# rlabTT.net
KiCad netlist of a schematic drawn in EAGLE
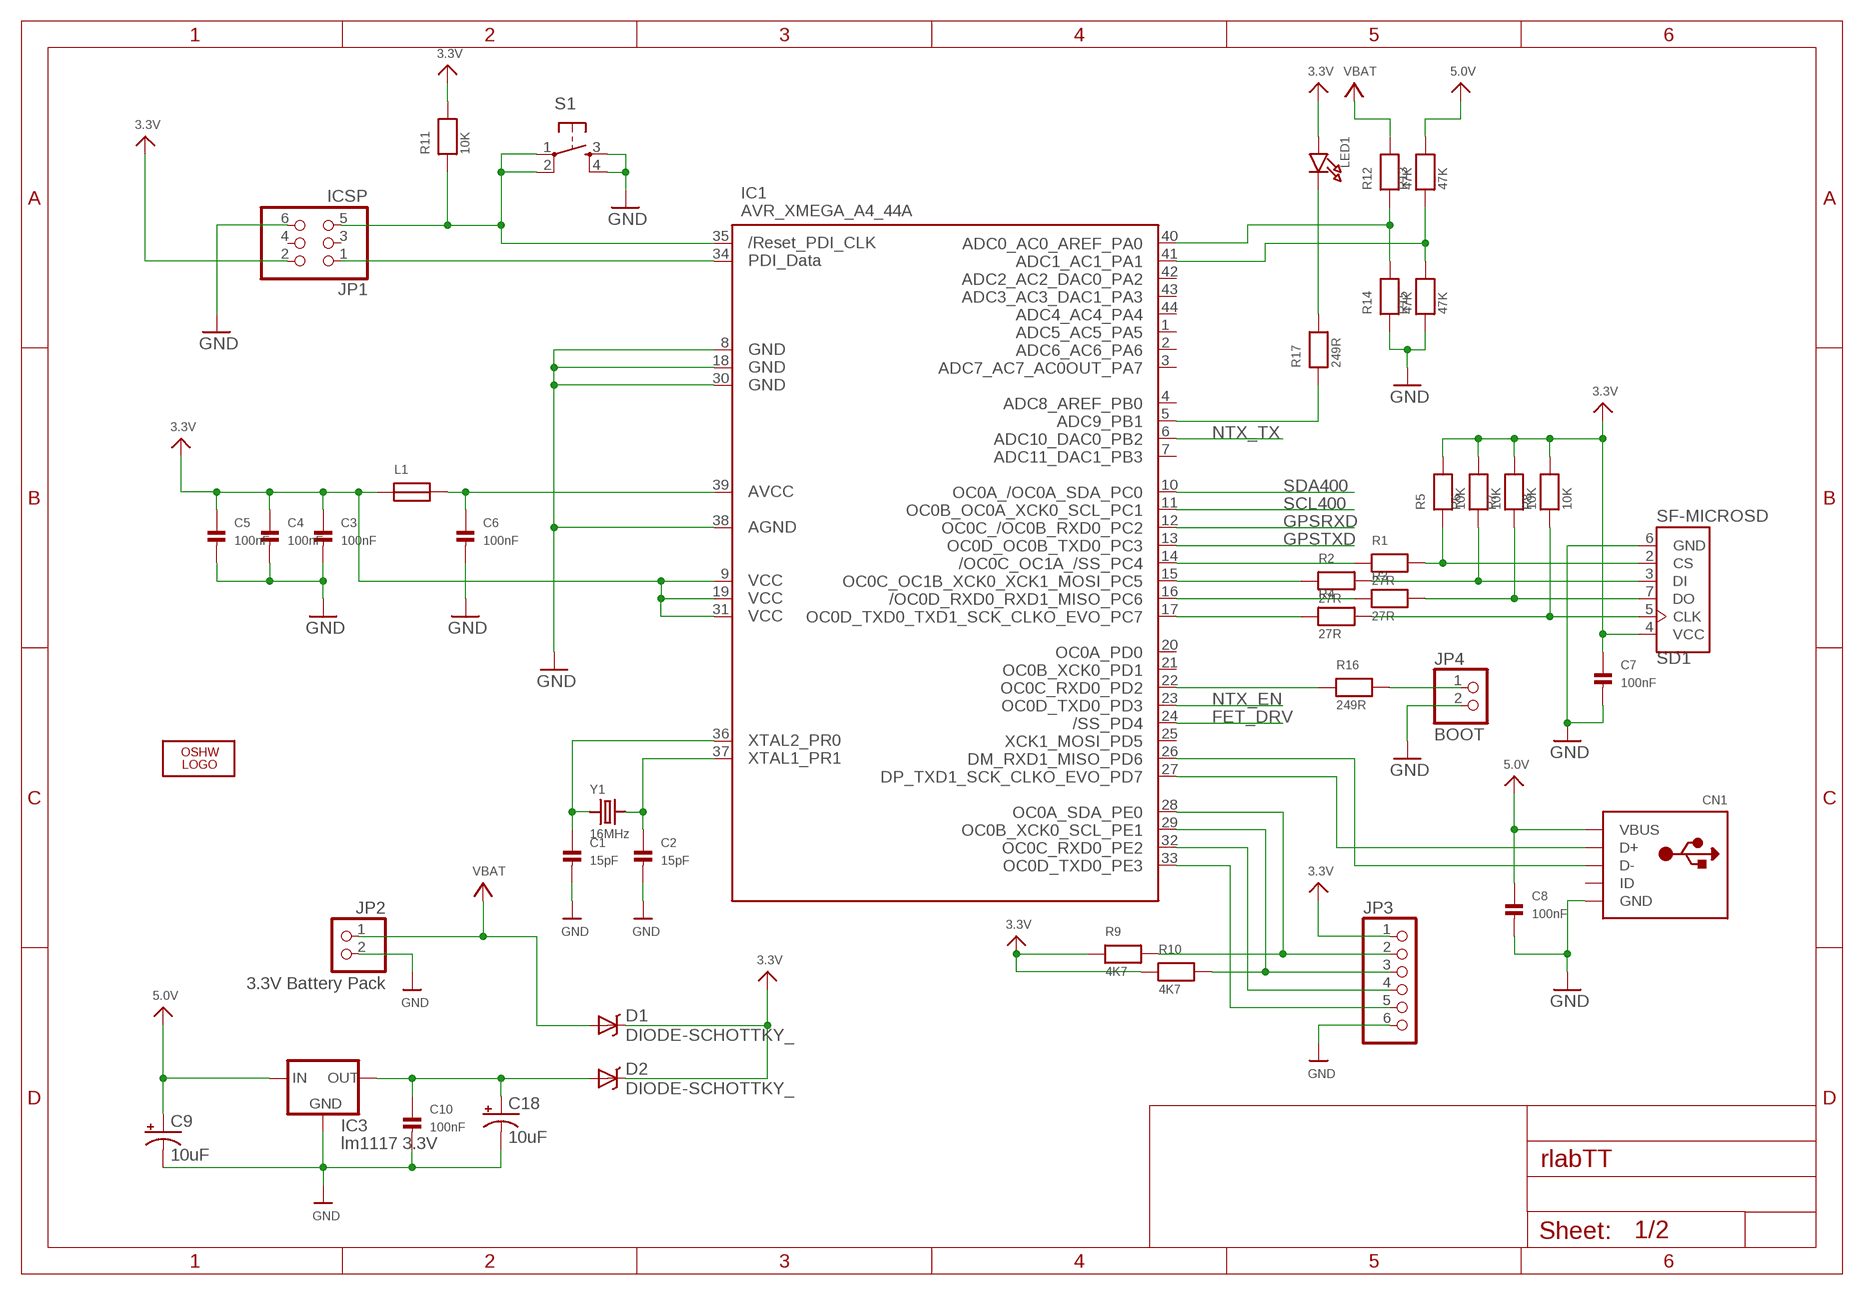
[diagram p0: schematic, sheet 1]
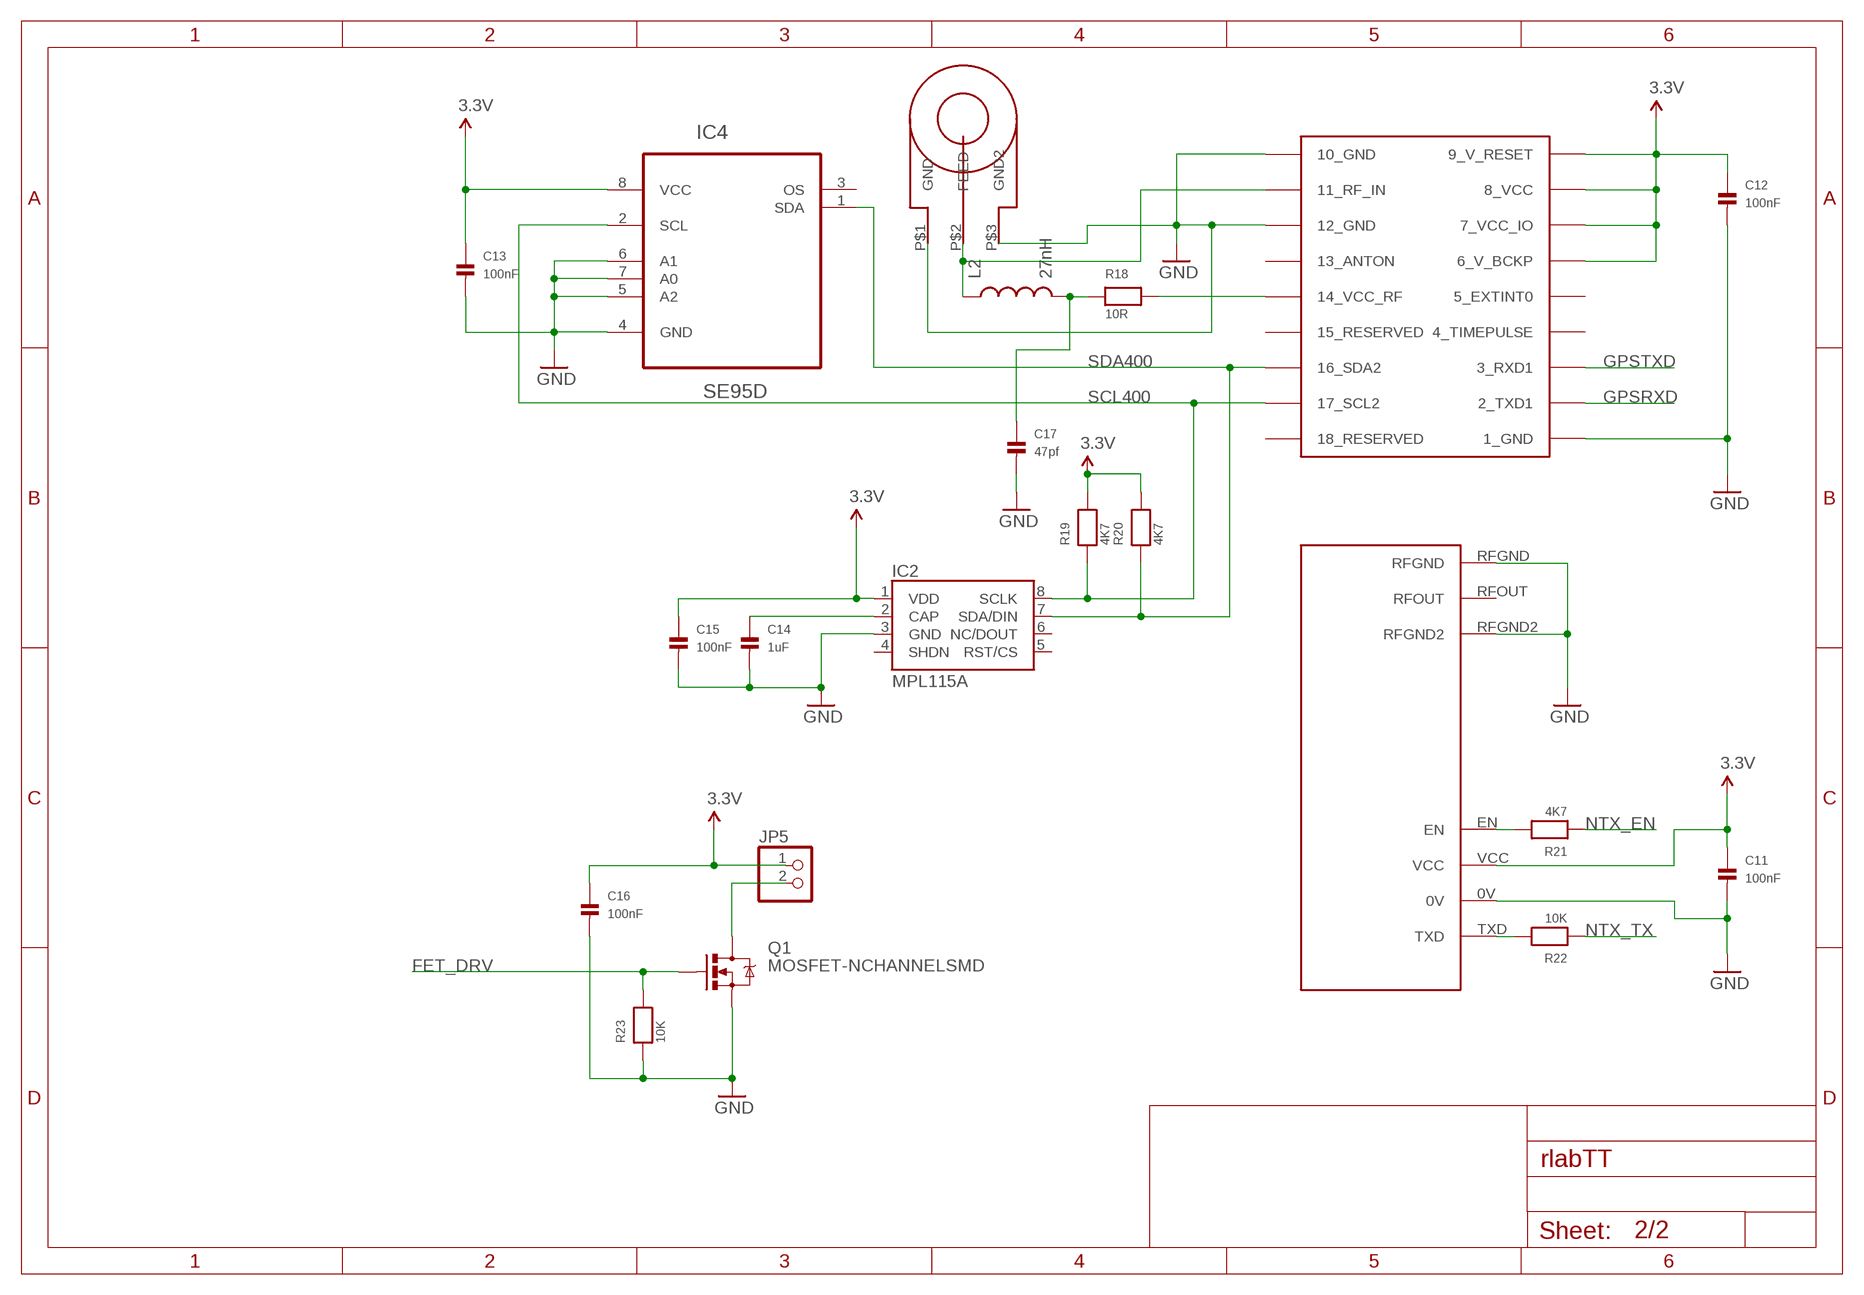
[diagram p1: schematic, sheet 2]

(export (version "E")
  (design (tool "Eeschema 10.0.6"))
  (components
    (comp (ref "C1")
      (value "15pF")
      (footprint "eagle-import:0603")
      (libsource (lib "eagle-import") (part "CAP_CERAMIC0603"))
    )
    (comp (ref "C2")
      (value "15pF")
      (footprint "eagle-import:0603")
      (libsource (lib "eagle-import") (part "CAP_CERAMIC0603"))
    )
    (comp (ref "C3")
      (value "100nF")
      (footprint "eagle-import:0603")
      (libsource (lib "eagle-import") (part "CAP_CERAMIC0603"))
    )
    (comp (ref "C4")
      (value "100nF")
      (footprint "eagle-import:0603")
      (libsource (lib "eagle-import") (part "CAP_CERAMIC0603"))
    )
    (comp (ref "C5")
      (value "100nF")
      (footprint "eagle-import:0603")
      (libsource (lib "eagle-import") (part "CAP_CERAMIC0603"))
    )
    (comp (ref "C6")
      (value "100nF")
      (footprint "eagle-import:0603")
      (libsource (lib "eagle-import") (part "CAP_CERAMIC0603"))
    )
    (comp (ref "C7")
      (value "100nF")
      (footprint "eagle-import:0603")
      (libsource (lib "eagle-import") (part "CAP_CERAMIC0603"))
    )
    (comp (ref "C8")
      (value "100nF")
      (footprint "eagle-import:0603")
      (libsource (lib "eagle-import") (part "CAP_CERAMIC0603"))
    )
    (comp (ref "C9")
      (value "10uF")
      (footprint "eagle-import:EIA3528")
      (libsource (lib "eagle-import") (part "CAP_POL3528"))
    )
    (comp (ref "C10")
      (value "100nF")
      (footprint "eagle-import:0603")
      (libsource (lib "eagle-import") (part "CAP_CERAMIC0603"))
    )
    (comp (ref "C18")
      (value "10uF")
      (footprint "eagle-import:EIA3528")
      (libsource (lib "eagle-import") (part "CAP_POL3528"))
    )
    (comp (ref "CN1")
      (value "USBMINIB")
      (footprint "eagle-import:USB-MINIB")
      (libsource (lib "eagle-import") (part "USBMINIB"))
    )
    (comp (ref "D1")
      (value "DIODE-SCHOTTKY_")
      (footprint "eagle-import:SMA-DIODE")
      (libsource (lib "eagle-import") (part "DIODE-SCHOTTKY_"))
    )
    (comp (ref "D2")
      (value "DIODE-SCHOTTKY_")
      (footprint "eagle-import:SMA-DIODE")
      (libsource (lib "eagle-import") (part "DIODE-SCHOTTKY_"))
    )
    (comp (ref "IC1")
      (value "AVR_XMEGA_A4_44A")
      (footprint "eagle-import:TQFP44")
      (libsource (lib "eagle-import") (part "AVR_XMEGA_A4_44A"))
    )
    (comp (ref "IC3")
      (value "lm1117 3.3V")
      (footprint "eagle-import:SOT223")
      (libsource (lib "eagle-import") (part "LM1117"))
    )
    (comp (ref "JP1")
      (value "ICSP")
      (footprint "eagle-import:2X03_90")
      (libsource (lib "eagle-import") (part "PINHD-2X3/90"))
    )
    (comp (ref "JP2")
      (value "3.3V Battery Pack")
      (footprint "eagle-import:1X02_90")
      (libsource (lib "eagle-import") (part "PINHD-1X2/90"))
    )
    (comp (ref "JP3")
      (value "PINHD-1X6/90")
      (footprint "eagle-import:1X06_90")
      (libsource (lib "eagle-import") (part "PINHD-1X6/90"))
    )
    (comp (ref "JP4")
      (value "BOOT")
      (footprint "eagle-import:1X02_90")
      (libsource (lib "eagle-import") (part "PINHD-1X2/90"))
    )
    (comp (ref "L1")
      (value "FERRITE")
      (footprint "eagle-import:0603")
      (libsource (lib "eagle-import") (part "FERRITE"))
    )
    (comp (ref "LED1")
      (value "LED0603")
      (footprint "eagle-import:CHIPLED_0603")
      (libsource (lib "eagle-import") (part "LED0603"))
    )
    (comp (ref "LOGO1")
      (value "OSHW_LOGO_8MILX0150-NT")
      (footprint "eagle-import:OSHW_8X150_NOTEXT")
      (libsource (lib "eagle-import") (part "OSHW_LOGO_8MILX0150-NT"))
    )
    (comp (ref "R1")
      (value "27R")
      (footprint "eagle-import:0603")
      (libsource (lib "eagle-import") (part "RESISTOR0603"))
    )
    (comp (ref "R2")
      (value "27R")
      (footprint "eagle-import:0603")
      (libsource (lib "eagle-import") (part "RESISTOR0603"))
    )
    (comp (ref "R3")
      (value "27R")
      (footprint "eagle-import:0603")
      (libsource (lib "eagle-import") (part "RESISTOR0603"))
    )
    (comp (ref "R4")
      (value "27R")
      (footprint "eagle-import:0603")
      (libsource (lib "eagle-import") (part "RESISTOR0603"))
    )
    (comp (ref "R5")
      (value "10K")
      (footprint "eagle-import:0603")
      (libsource (lib "eagle-import") (part "RESISTOR0603"))
    )
    (comp (ref "R6")
      (value "10K")
      (footprint "eagle-import:0603")
      (libsource (lib "eagle-import") (part "RESISTOR0603"))
    )
    (comp (ref "R7")
      (value "10K")
      (footprint "eagle-import:0603")
      (libsource (lib "eagle-import") (part "RESISTOR0603"))
    )
    (comp (ref "R8")
      (value "10K")
      (footprint "eagle-import:0603")
      (libsource (lib "eagle-import") (part "RESISTOR0603"))
    )
    (comp (ref "R9")
      (value "4K7")
      (footprint "eagle-import:0603")
      (libsource (lib "eagle-import") (part "RESISTOR0603"))
    )
    (comp (ref "R10")
      (value "4K7")
      (footprint "eagle-import:0603")
      (libsource (lib "eagle-import") (part "RESISTOR0603"))
    )
    (comp (ref "R11")
      (value "10K")
      (footprint "eagle-import:0603")
      (libsource (lib "eagle-import") (part "RESISTOR0603"))
    )
    (comp (ref "R12")
      (value "47K")
      (footprint "eagle-import:0603")
      (libsource (lib "eagle-import") (part "RESISTOR0603"))
    )
    (comp (ref "R13")
      (value "47K")
      (footprint "eagle-import:0603")
      (libsource (lib "eagle-import") (part "RESISTOR0603"))
    )
    (comp (ref "R14")
      (value "47K")
      (footprint "eagle-import:0603")
      (libsource (lib "eagle-import") (part "RESISTOR0603"))
    )
    (comp (ref "R15")
      (value "47K")
      (footprint "eagle-import:0603")
      (libsource (lib "eagle-import") (part "RESISTOR0603"))
    )
    (comp (ref "R16")
      (value "249R")
      (footprint "eagle-import:0603")
      (libsource (lib "eagle-import") (part "RESISTOR0603"))
    )
    (comp (ref "R17")
      (value "249R")
      (footprint "eagle-import:0603")
      (libsource (lib "eagle-import") (part "RESISTOR0603"))
    )
    (comp (ref "S1")
      (value "TAC_SWITCHSMD")
      (footprint "eagle-import:TACTILE_SWITCH_SMD")
      (libsource (lib "eagle-import") (part "TAC_SWITCHSMD"))
    )
    (comp (ref "SD1")
      (value "SF-MICROSD")
      (footprint "eagle-import:MICROSD")
      (libsource (lib "eagle-import") (part "SF-MICROSD"))
    )
    (comp (ref "Y1")
      (value "16MHz")
      (footprint "eagle-import:CRYSTAL_3.2X2.5")
      (libsource (lib "eagle-import") (part "CRYSTALTHIN"))
    )
    (comp (ref "C11")
      (value "100nF")
      (footprint "eagle-import:0603")
      (libsource (lib "eagle-import") (part "CAP_CERAMIC0603"))
    )
    (comp (ref "C12")
      (value "100nF")
      (footprint "eagle-import:0603")
      (libsource (lib "eagle-import") (part "CAP_CERAMIC0603"))
    )
    (comp (ref "C13")
      (value "100nF")
      (footprint "eagle-import:0603")
      (libsource (lib "eagle-import") (part "CAP_CERAMIC0603"))
    )
    (comp (ref "C14")
      (value "1uF")
      (footprint "eagle-import:0603")
      (libsource (lib "eagle-import") (part "CAP_CERAMIC0603"))
    )
    (comp (ref "C15")
      (value "100nF")
      (footprint "eagle-import:0603")
      (libsource (lib "eagle-import") (part "CAP_CERAMIC0603"))
    )
    (comp (ref "C16")
      (value "100nF")
      (footprint "eagle-import:0603")
      (libsource (lib "eagle-import") (part "CAP_CERAMIC0603"))
    )
    (comp (ref "C17")
      (value "47pf")
      (footprint "eagle-import:0603")
      (libsource (lib "eagle-import") (part "CAP_CERAMIC0603"))
    )
    (comp (ref "IC2")
      (value "MPL115A")
      (footprint "eagle-import:LGA8")
      (libsource (lib "eagle-import") (part "MPL115A"))
    )
    (comp (ref "IC4")
      (value "SE95D")
      (footprint "eagle-import:SOIC127P600X175-8N")
      (libsource (lib "eagle-import") (part "SE95D"))
    )
    (comp (ref "JP5")
      (value "PINHD-1X2/90")
      (footprint "eagle-import:1X02_90")
      (libsource (lib "eagle-import") (part "PINHD-1X2/90"))
    )
    (comp (ref "L2")
      (value "27nH")
      (footprint "eagle-import:0603")
      (libsource (lib "eagle-import") (part "INDUCTOR0603"))
    )
    (comp (ref "Q1")
      (value "MOSFET-NCHANNELSMD")
      (footprint "eagle-import:SOT23-3")
      (libsource (lib "eagle-import") (part "MOSFET-NCHANNELSMD"))
    )
    (comp (ref "R18")
      (value "10R")
      (footprint "eagle-import:0603")
      (libsource (lib "eagle-import") (part "RESISTOR0603"))
    )
    (comp (ref "R19")
      (value "4K7")
      (footprint "eagle-import:0603")
      (libsource (lib "eagle-import") (part "RESISTOR0603"))
    )
    (comp (ref "R20")
      (value "4K7")
      (footprint "eagle-import:0603")
      (libsource (lib "eagle-import") (part "RESISTOR0603"))
    )
    (comp (ref "R21")
      (value "4K7")
      (footprint "eagle-import:0603")
      (libsource (lib "eagle-import") (part "RESISTOR0603"))
    )
    (comp (ref "R22")
      (value "10K")
      (footprint "eagle-import:0603")
      (libsource (lib "eagle-import") (part "RESISTOR0603"))
    )
    (comp (ref "R23")
      (value "10K")
      (footprint "eagle-import:0603")
      (libsource (lib "eagle-import") (part "RESISTOR0603"))
    )
    (comp (ref "U1")
      (value "UBLOX_MAX")
      (footprint "eagle-import:UBLOX_MAX")
      (libsource (lib "eagle-import") (part "UBLOX_MAX"))
    )
    (comp (ref "U2")
      (value "NTX2")
      (footprint "eagle-import:NTX2")
      (libsource (lib "eagle-import") (part "NTX2"))
    )
    (comp (ref "U3")
      (value "SARANTEL-SL1250")
      (footprint "eagle-import:SARANTEL-SL1250")
      (libsource (lib "eagle-import") (part "SARANTEL-SL1250"))
    )
  )
  (nets
    (net (code "1") (name "3.3V") (class "Default")
      (node (ref "C11") (pin "1") (pinfunction "P$1_1") (pintype "passive"))
      (node (ref "C12") (pin "1") (pinfunction "P$1_1") (pintype "passive"))
      (node (ref "C13") (pin "1") (pinfunction "P$1_1") (pintype "passive"))
      (node (ref "C15") (pin "1") (pinfunction "P$1_1") (pintype "passive"))
      (node (ref "C16") (pin "1") (pinfunction "P$1_1") (pintype "passive"))
      (node (ref "C3") (pin "1") (pinfunction "P$1_1") (pintype "passive"))
      (node (ref "C4") (pin "1") (pinfunction "P$1_1") (pintype "passive"))
      (node (ref "C5") (pin "1") (pinfunction "P$1_1") (pintype "passive"))
      (node (ref "C7") (pin "1") (pinfunction "P$1_1") (pintype "passive"))
      (node (ref "D1") (pin "C") (pinfunction "C_C") (pintype "passive"))
      (node (ref "D2") (pin "C") (pinfunction "C_C") (pintype "passive"))
      (node (ref "IC1") (pin "19") (pinfunction "VCC2_19") (pintype "bidirectional"))
      (node (ref "IC1") (pin "31") (pinfunction "VCC3_31") (pintype "bidirectional"))
      (node (ref "IC1") (pin "9") (pinfunction "VCC1_9") (pintype "bidirectional"))
      (node (ref "IC2") (pin "1") (pinfunction "VDD_1") (pintype "bidirectional"))
      (node (ref "IC4") (pin "8") (pinfunction "VCC_8") (pintype "power_in"))
      (node (ref "JP1") (pin "2") (pinfunction "2_2") (pintype "passive"))
      (node (ref "JP3") (pin "1") (pinfunction "1_1") (pintype "passive"))
      (node (ref "JP5") (pin "1") (pinfunction "1_1") (pintype "passive"))
      (node (ref "L1") (pin "1") (pinfunction "P$1_1") (pintype "bidirectional"))
      (node (ref "LED1") (pin "A") (pinfunction "A_A") (pintype "passive"))
      (node (ref "R10") (pin "1") (pinfunction "1_1") (pintype "passive"))
      (node (ref "R11") (pin "2") (pinfunction "2_2") (pintype "passive"))
      (node (ref "R19") (pin "2") (pinfunction "2_2") (pintype "passive"))
      (node (ref "R20") (pin "2") (pinfunction "2_2") (pintype "passive"))
      (node (ref "R5") (pin "2") (pinfunction "2_2") (pintype "passive"))
      (node (ref "R6") (pin "2") (pinfunction "2_2") (pintype "passive"))
      (node (ref "R7") (pin "2") (pinfunction "2_2") (pintype "passive"))
      (node (ref "R8") (pin "2") (pinfunction "2_2") (pintype "passive"))
      (node (ref "R9") (pin "1") (pinfunction "1_1") (pintype "passive"))
      (node (ref "SD1") (pin "4") (pinfunction "VCC_4") (pintype "passive"))
      (node (ref "U1") (pin "6_V_BCKP") (pinfunction "6_V_BCKP_6_V_BCKP") (pintype "bidirectional"))
      (node (ref "U1") (pin "7_VCC_IO") (pinfunction "7_VCC_IO_7_VCC_IO") (pintype "power_in"))
      (node (ref "U1") (pin "8_VCC") (pinfunction "8_VCC_8_VCC") (pintype "power_in"))
      (node (ref "U1") (pin "9_V_RESET") (pinfunction "9_V_RESET_9_V_RESET") (pintype "power_in"))
      (node (ref "U2") (pin "VCC") (pinfunction "VCC_VCC") (pintype "bidirectional"))
    )
    (net (code "2") (name "5.0V") (class "Default")
      (node (ref "C8") (pin "1") (pinfunction "P$1_1") (pintype "passive"))
      (node (ref "C9") (pin "A") (pinfunction "+_A") (pintype "passive"))
      (node (ref "CN1") (pin "VBUS") (pinfunction "VBUS_VBUS") (pintype "power_in"))
      (node (ref "IC3") (pin "3") (pinfunction "IN_3") (pintype "input"))
      (node (ref "R13") (pin "2") (pinfunction "2_2") (pintype "passive"))
    )
    (net (code "3") (name "FET_DRV") (class "Default")
      (node (ref "IC1") (pin "24") (pinfunction "PD4_24") (pintype "bidirectional"))
      (node (ref "Q1") (pin "1") (pinfunction "G_1") (pintype "passive"))
      (node (ref "R23") (pin "2") (pinfunction "2_2") (pintype "passive"))
    )
    (net (code "4") (name "GND") (class "Default")
      (node (ref "C1") (pin "2") (pinfunction "P$2_2") (pintype "passive"))
      (node (ref "C10") (pin "2") (pinfunction "P$2_2") (pintype "passive"))
      (node (ref "C11") (pin "2") (pinfunction "P$2_2") (pintype "passive"))
      (node (ref "C12") (pin "2") (pinfunction "P$2_2") (pintype "passive"))
      (node (ref "C13") (pin "2") (pinfunction "P$2_2") (pintype "passive"))
      (node (ref "C14") (pin "2") (pinfunction "P$2_2") (pintype "passive"))
      (node (ref "C15") (pin "2") (pinfunction "P$2_2") (pintype "passive"))
      (node (ref "C16") (pin "2") (pinfunction "P$2_2") (pintype "passive"))
      (node (ref "C17") (pin "2") (pinfunction "P$2_2") (pintype "passive"))
      (node (ref "C18") (pin "C") (pinfunction "-_C") (pintype "passive"))
      (node (ref "C2") (pin "2") (pinfunction "P$2_2") (pintype "passive"))
      (node (ref "C3") (pin "2") (pinfunction "P$2_2") (pintype "passive"))
      (node (ref "C4") (pin "2") (pinfunction "P$2_2") (pintype "passive"))
      (node (ref "C5") (pin "2") (pinfunction "P$2_2") (pintype "passive"))
      (node (ref "C6") (pin "2") (pinfunction "P$2_2") (pintype "passive"))
      (node (ref "C7") (pin "2") (pinfunction "P$2_2") (pintype "passive"))
      (node (ref "C8") (pin "2") (pinfunction "P$2_2") (pintype "passive"))
      (node (ref "C9") (pin "C") (pinfunction "-_C") (pintype "passive"))
      (node (ref "CN1") (pin "GND") (pinfunction "GND_GND") (pintype "power_in"))
      (node (ref "IC1") (pin "18") (pinfunction "GND2_18") (pintype "bidirectional"))
      (node (ref "IC1") (pin "30") (pinfunction "GND3_30") (pintype "bidirectional"))
      (node (ref "IC1") (pin "38") (pinfunction "AGND_38") (pintype "bidirectional"))
      (node (ref "IC1") (pin "8") (pinfunction "GND1_8") (pintype "bidirectional"))
      (node (ref "IC2") (pin "3") (pinfunction "GND_3") (pintype "bidirectional"))
      (node (ref "IC3") (pin "1") (pinfunction "GND_1") (pintype "input"))
      (node (ref "IC4") (pin "4") (pinfunction "GND_4") (pintype "passive"))
      (node (ref "IC4") (pin "5") (pinfunction "A2_5") (pintype "input"))
      (node (ref "IC4") (pin "6") (pinfunction "A1_6") (pintype "input"))
      (node (ref "IC4") (pin "7") (pinfunction "A0_7") (pintype "input"))
      (node (ref "JP1") (pin "6") (pinfunction "6_6") (pintype "passive"))
      (node (ref "JP2") (pin "2") (pinfunction "2_2") (pintype "passive"))
      (node (ref "JP3") (pin "6") (pinfunction "6_6") (pintype "passive"))
      (node (ref "JP4") (pin "2") (pinfunction "2_2") (pintype "passive"))
      (node (ref "Q1") (pin "2") (pinfunction "S_2") (pintype "passive"))
      (node (ref "R14") (pin "1") (pinfunction "1_1") (pintype "passive"))
      (node (ref "R15") (pin "1") (pinfunction "1_1") (pintype "passive"))
      (node (ref "R23") (pin "1") (pinfunction "1_1") (pintype "passive"))
      (node (ref "S1") (pin "3") (pinfunction "3_3") (pintype "passive"))
      (node (ref "S1") (pin "4") (pinfunction "4_4") (pintype "passive"))
      (node (ref "SD1") (pin "6") (pinfunction "GND_6") (pintype "power_in"))
      (node (ref "U1") (pin "10_GND") (pinfunction "10_GND_10_GND") (pintype "power_in"))
      (node (ref "U1") (pin "12_GND") (pinfunction "12_GND_12_GND") (pintype "power_in"))
      (node (ref "U1") (pin "1_GND") (pinfunction "1_GND_1_GND") (pintype "power_in"))
      (node (ref "U2") (pin "0V") (pinfunction "0V_0V") (pintype "bidirectional"))
      (node (ref "U2") (pin "RFGND") (pinfunction "RFGND_RFGND") (pintype "bidirectional"))
      (node (ref "U2") (pin "RFGND2") (pinfunction "RFGND2_RFGND2") (pintype "bidirectional"))
      (node (ref "U3") (pin "P$1") (pinfunction "GND_P$1") (pintype "bidirectional"))
      (node (ref "U3") (pin "P$3") (pinfunction "GND2_P$3") (pintype "bidirectional"))
    )
    (net (code "5") (name "GPSRXD") (class "Default")
      (node (ref "IC1") (pin "12") (pinfunction "PC2_12") (pintype "bidirectional"))
      (node (ref "U1") (pin "2_TXD1") (pinfunction "2_TXD1_2_TXD1") (pintype "bidirectional"))
    )
    (net (code "6") (name "GPSTXD") (class "Default")
      (node (ref "IC1") (pin "13") (pinfunction "PC3_13") (pintype "bidirectional"))
      (node (ref "U1") (pin "3_RXD1") (pinfunction "3_RXD1_3_RXD1") (pintype "bidirectional"))
    )
    (net (code "7") (name "NTX_EN") (class "Default")
      (node (ref "IC1") (pin "23") (pinfunction "PD3_23") (pintype "bidirectional"))
      (node (ref "R21") (pin "1") (pinfunction "1_1") (pintype "passive"))
    )
    (net (code "8") (name "NTX_TX") (class "Default")
      (node (ref "IC1") (pin "6") (pinfunction "PB2_6") (pintype "bidirectional"))
      (node (ref "R22") (pin "1") (pinfunction "1_1") (pintype "passive"))
    )
    (net (code "9") (name "Net-(C1-P$1)") (class "Default")
      (node (ref "C1") (pin "1") (pinfunction "P$1_1") (pintype "passive"))
      (node (ref "IC1") (pin "36") (pinfunction "PR0_36") (pintype "bidirectional"))
      (node (ref "Y1") (pin "1") (pinfunction "1_1") (pintype "passive"))
    )
    (net (code "10") (name "Net-(C2-P$1)") (class "Default")
      (node (ref "C2") (pin "1") (pinfunction "P$1_1") (pintype "passive"))
      (node (ref "IC1") (pin "37") (pinfunction "PR1_37") (pintype "bidirectional"))
      (node (ref "Y1") (pin "2") (pinfunction "2_2") (pintype "passive"))
    )
    (net (code "11") (name "Net-(C6-P$1)") (class "Default")
      (node (ref "C6") (pin "1") (pinfunction "P$1_1") (pintype "passive"))
      (node (ref "IC1") (pin "39") (pinfunction "AVCC_39") (pintype "bidirectional"))
      (node (ref "L1") (pin "2") (pinfunction "P$2_2") (pintype "bidirectional"))
    )
    (net (code "12") (name "Net-(C10-P$1)") (class "Default")
      (node (ref "C10") (pin "1") (pinfunction "P$1_1") (pintype "passive"))
      (node (ref "C18") (pin "A") (pinfunction "+_A") (pintype "passive"))
      (node (ref "D2") (pin "A") (pinfunction "A_A") (pintype "passive"))
      (node (ref "IC3") (pin "2") (pinfunction "OUT_2") (pintype "passive"))
    )
    (net (code "13") (name "Net-(C14-P$1)") (class "Default")
      (node (ref "C14") (pin "1") (pinfunction "P$1_1") (pintype "passive"))
      (node (ref "IC2") (pin "2") (pinfunction "CAP_2") (pintype "bidirectional"))
    )
    (net (code "14") (name "Net-(C17-P$1)") (class "Default")
      (node (ref "C17") (pin "1") (pinfunction "P$1_1") (pintype "passive"))
      (node (ref "L2") (pin "2") (pinfunction "2_2") (pintype "passive"))
      (node (ref "R18") (pin "1") (pinfunction "1_1") (pintype "passive"))
    )
    (net (code "15") (name "Net-(IC1-PA0)") (class "Default")
      (node (ref "IC1") (pin "40") (pinfunction "PA0_40") (pintype "bidirectional"))
      (node (ref "R12") (pin "1") (pinfunction "1_1") (pintype "passive"))
      (node (ref "R14") (pin "2") (pinfunction "2_2") (pintype "passive"))
    )
    (net (code "16") (name "Net-(IC1-PA1)") (class "Default")
      (node (ref "IC1") (pin "41") (pinfunction "PA1_41") (pintype "bidirectional"))
      (node (ref "R13") (pin "1") (pinfunction "1_1") (pintype "passive"))
      (node (ref "R15") (pin "2") (pinfunction "2_2") (pintype "passive"))
    )
    (net (code "17") (name "Net-(IC1-PB1)") (class "Default")
      (node (ref "IC1") (pin "5") (pinfunction "PB1_5") (pintype "bidirectional"))
      (node (ref "R17") (pin "1") (pinfunction "1_1") (pintype "passive"))
    )
    (net (code "18") (name "Net-(IC1-PC4)") (class "Default")
      (node (ref "IC1") (pin "14") (pinfunction "PC4_14") (pintype "bidirectional"))
      (node (ref "R1") (pin "1") (pinfunction "1_1") (pintype "passive"))
    )
    (net (code "19") (name "Net-(IC1-PC5)") (class "Default")
      (node (ref "IC1") (pin "15") (pinfunction "PC5_15") (pintype "bidirectional"))
      (node (ref "R2") (pin "1") (pinfunction "1_1") (pintype "passive"))
    )
    (net (code "20") (name "Net-(IC1-PC6)") (class "Default")
      (node (ref "IC1") (pin "16") (pinfunction "PC6_16") (pintype "bidirectional"))
      (node (ref "R3") (pin "1") (pinfunction "1_1") (pintype "passive"))
    )
    (net (code "21") (name "Net-(IC1-PC7)") (class "Default")
      (node (ref "IC1") (pin "17") (pinfunction "PC7_17") (pintype "bidirectional"))
      (node (ref "R4") (pin "1") (pinfunction "1_1") (pintype "passive"))
    )
    (net (code "22") (name "Net-(IC1-PD2)") (class "Default")
      (node (ref "IC1") (pin "22") (pinfunction "PD2_22") (pintype "bidirectional"))
      (node (ref "R16") (pin "1") (pinfunction "1_1") (pintype "passive"))
    )
    (net (code "23") (name "Net-(IC1-PD6)") (class "Default")
      (node (ref "CN1") (pin "D-") (pinfunction "D-_D-") (pintype "bidirectional"))
      (node (ref "IC1") (pin "26") (pinfunction "PD6_26") (pintype "bidirectional"))
    )
    (net (code "24") (name "Net-(IC1-PD7)") (class "Default")
      (node (ref "CN1") (pin "D+") (pinfunction "D+_D+") (pintype "bidirectional"))
      (node (ref "IC1") (pin "27") (pinfunction "PD7_27") (pintype "bidirectional"))
    )
    (net (code "25") (name "Net-(IC1-PDI_DATA)") (class "Default")
      (node (ref "IC1") (pin "34") (pinfunction "PDI_DATA_34") (pintype "bidirectional"))
      (node (ref "JP1") (pin "1") (pinfunction "1_1") (pintype "passive"))
    )
    (net (code "26") (name "Net-(IC1-PE0)") (class "Default")
      (node (ref "IC1") (pin "28") (pinfunction "PE0_28") (pintype "bidirectional"))
      (node (ref "JP3") (pin "2") (pinfunction "2_2") (pintype "passive"))
      (node (ref "R9") (pin "2") (pinfunction "2_2") (pintype "passive"))
    )
    (net (code "27") (name "Net-(IC1-PE1)") (class "Default")
      (node (ref "IC1") (pin "29") (pinfunction "PE1_29") (pintype "bidirectional"))
      (node (ref "JP3") (pin "3") (pinfunction "3_3") (pintype "passive"))
      (node (ref "R10") (pin "2") (pinfunction "2_2") (pintype "passive"))
    )
    (net (code "28") (name "Net-(IC1-PE2)") (class "Default")
      (node (ref "IC1") (pin "32") (pinfunction "PE2_32") (pintype "bidirectional"))
      (node (ref "JP3") (pin "4") (pinfunction "4_4") (pintype "passive"))
    )
    (net (code "29") (name "Net-(IC1-PE3)") (class "Default")
      (node (ref "IC1") (pin "33") (pinfunction "PE3_33") (pintype "bidirectional"))
      (node (ref "JP3") (pin "5") (pinfunction "5_5") (pintype "passive"))
    )
    (net (code "30") (name "Net-(IC1-RESET)") (class "Default")
      (node (ref "IC1") (pin "35") (pinfunction "RESET_35") (pintype "bidirectional"))
      (node (ref "JP1") (pin "5") (pinfunction "5_5") (pintype "passive"))
      (node (ref "R11") (pin "1") (pinfunction "1_1") (pintype "passive"))
      (node (ref "S1") (pin "1") (pinfunction "1_1") (pintype "passive"))
      (node (ref "S1") (pin "2") (pinfunction "2_2") (pintype "passive"))
    )
    (net (code "31") (name "Net-(JP4-Pad1)") (class "Default")
      (node (ref "JP4") (pin "1") (pinfunction "1_1") (pintype "passive"))
      (node (ref "R16") (pin "2") (pinfunction "2_2") (pintype "passive"))
    )
    (net (code "32") (name "Net-(LED1-PadC)") (class "Default")
      (node (ref "LED1") (pin "C") (pinfunction "C_C") (pintype "passive"))
      (node (ref "R17") (pin "2") (pinfunction "2_2") (pintype "passive"))
    )
    (net (code "33") (name "Net-(Q1-D)") (class "Default")
      (node (ref "JP5") (pin "2") (pinfunction "2_2") (pintype "passive"))
      (node (ref "Q1") (pin "3") (pinfunction "D_3") (pintype "passive"))
    )
    (net (code "34") (name "Net-(R18-Pad2)") (class "Default")
      (node (ref "R18") (pin "2") (pinfunction "2_2") (pintype "passive"))
      (node (ref "U1") (pin "14_VCC_RF") (pinfunction "14_VCC_RF_14_VCC_RF") (pintype "bidirectional"))
    )
    (net (code "35") (name "Net-(R21-Pad2)") (class "Default")
      (node (ref "R21") (pin "2") (pinfunction "2_2") (pintype "passive"))
      (node (ref "U2") (pin "EN") (pinfunction "EN_EN") (pintype "bidirectional"))
    )
    (net (code "36") (name "Net-(R22-Pad2)") (class "Default")
      (node (ref "R22") (pin "2") (pinfunction "2_2") (pintype "passive"))
      (node (ref "U2") (pin "TXD") (pinfunction "TXD_TXD") (pintype "bidirectional"))
    )
    (net (code "37") (name "Net-(SD1-CLK)") (class "Default")
      (node (ref "R4") (pin "2") (pinfunction "2_2") (pintype "passive"))
      (node (ref "R8") (pin "1") (pinfunction "1_1") (pintype "passive"))
      (node (ref "SD1") (pin "5") (pinfunction "CLK_5") (pintype "bidirectional"))
    )
    (net (code "38") (name "Net-(SD1-CS)") (class "Default")
      (node (ref "R1") (pin "2") (pinfunction "2_2") (pintype "passive"))
      (node (ref "R5") (pin "1") (pinfunction "1_1") (pintype "passive"))
      (node (ref "SD1") (pin "2") (pinfunction "CS_2") (pintype "bidirectional"))
    )
    (net (code "39") (name "Net-(SD1-DI)") (class "Default")
      (node (ref "R2") (pin "2") (pinfunction "2_2") (pintype "passive"))
      (node (ref "R6") (pin "1") (pinfunction "1_1") (pintype "passive"))
      (node (ref "SD1") (pin "3") (pinfunction "DI_3") (pintype "bidirectional"))
    )
    (net (code "40") (name "Net-(SD1-DO)") (class "Default")
      (node (ref "R3") (pin "2") (pinfunction "2_2") (pintype "passive"))
      (node (ref "R7") (pin "1") (pinfunction "1_1") (pintype "passive"))
      (node (ref "SD1") (pin "7") (pinfunction "DO_7") (pintype "bidirectional"))
    )
    (net (code "41") (name "Net-(U3-FEED)") (class "Default")
      (node (ref "L2") (pin "1") (pinfunction "1_1") (pintype "passive"))
      (node (ref "U1") (pin "11_RF_IN") (pinfunction "11_RF_IN_11_RF_IN") (pintype "bidirectional"))
      (node (ref "U3") (pin "P$2") (pinfunction "FEED_P$2") (pintype "bidirectional"))
    )
    (net (code "42") (name "SCL400") (class "Default")
      (node (ref "IC1") (pin "11") (pinfunction "PC1_11") (pintype "bidirectional"))
      (node (ref "IC2") (pin "8") (pinfunction "SCLK_8") (pintype "bidirectional"))
      (node (ref "IC4") (pin "2") (pinfunction "SCL_2") (pintype "input"))
      (node (ref "R19") (pin "1") (pinfunction "1_1") (pintype "passive"))
      (node (ref "U1") (pin "17_SCL2") (pinfunction "17_SCL2_17_SCL2") (pintype "bidirectional"))
    )
    (net (code "43") (name "SDA400") (class "Default")
      (node (ref "IC1") (pin "10") (pinfunction "PC0_10") (pintype "bidirectional"))
      (node (ref "IC2") (pin "7") (pinfunction "SDA/DIN_7") (pintype "bidirectional"))
      (node (ref "IC4") (pin "1") (pinfunction "SDA_1") (pintype "bidirectional"))
      (node (ref "R20") (pin "1") (pinfunction "1_1") (pintype "passive"))
      (node (ref "U1") (pin "16_SDA2") (pinfunction "16_SDA2_16_SDA2") (pintype "bidirectional"))
    )
    (net (code "44") (name "VBAT") (class "Default")
      (node (ref "D1") (pin "A") (pinfunction "A_A") (pintype "passive"))
      (node (ref "JP2") (pin "1") (pinfunction "1_1") (pintype "passive"))
      (node (ref "R12") (pin "2") (pinfunction "2_2") (pintype "passive"))
    )
    (net (code "45") (name "unconnected-(CN1-PadID)") (class "Default")
      (node (ref "CN1") (pin "ID") (pinfunction "ID_ID") (pintype "bidirectional"))
    )
    (net (code "46") (name "unconnected-(IC1-PA2-Pad42)") (class "Default")
      (node (ref "IC1") (pin "42") (pinfunction "PA2_42") (pintype "bidirectional"))
    )
    (net (code "47") (name "unconnected-(IC1-PA3-Pad43)") (class "Default")
      (node (ref "IC1") (pin "43") (pinfunction "PA3_43") (pintype "bidirectional"))
    )
    (net (code "48") (name "unconnected-(IC1-PA4-Pad44)") (class "Default")
      (node (ref "IC1") (pin "44") (pinfunction "PA4_44") (pintype "bidirectional"))
    )
    (net (code "49") (name "unconnected-(IC1-PA5-Pad1)") (class "Default")
      (node (ref "IC1") (pin "1") (pinfunction "PA5_1") (pintype "bidirectional"))
    )
    (net (code "50") (name "unconnected-(IC1-PA6-Pad2)") (class "Default")
      (node (ref "IC1") (pin "2") (pinfunction "PA6_2") (pintype "bidirectional"))
    )
    (net (code "51") (name "unconnected-(IC1-PA7-Pad3)") (class "Default")
      (node (ref "IC1") (pin "3") (pinfunction "PA7_3") (pintype "bidirectional"))
    )
    (net (code "52") (name "unconnected-(IC1-PB0-Pad4)") (class "Default")
      (node (ref "IC1") (pin "4") (pinfunction "PB0_4") (pintype "bidirectional"))
    )
    (net (code "53") (name "unconnected-(IC1-PB3-Pad7)") (class "Default")
      (node (ref "IC1") (pin "7") (pinfunction "PB3_7") (pintype "bidirectional"))
    )
    (net (code "54") (name "unconnected-(IC1-PD0-Pad20)") (class "Default")
      (node (ref "IC1") (pin "20") (pinfunction "PD0_20") (pintype "bidirectional"))
    )
    (net (code "55") (name "unconnected-(IC1-PD1-Pad21)") (class "Default")
      (node (ref "IC1") (pin "21") (pinfunction "PD1_21") (pintype "bidirectional"))
    )
    (net (code "56") (name "unconnected-(IC1-PD5-Pad25)") (class "Default")
      (node (ref "IC1") (pin "25") (pinfunction "PD5_25") (pintype "bidirectional"))
    )
    (net (code "57") (name "unconnected-(IC2-NC{slash}DOUT-Pad6)") (class "Default")
      (node (ref "IC2") (pin "6") (pinfunction "NC/DOUT_6") (pintype "bidirectional"))
    )
    (net (code "58") (name "unconnected-(IC2-RST{slash}CS-Pad5)") (class "Default")
      (node (ref "IC2") (pin "5") (pinfunction "RST/CS_5") (pintype "bidirectional"))
    )
    (net (code "59") (name "unconnected-(IC2-SHDN-Pad4)") (class "Default")
      (node (ref "IC2") (pin "4") (pinfunction "SHDN_4") (pintype "bidirectional"))
    )
    (net (code "60") (name "unconnected-(IC4-OS-Pad3)") (class "Default")
      (node (ref "IC4") (pin "3") (pinfunction "OS_3") (pintype "output"))
    )
    (net (code "61") (name "unconnected-(JP1-Pad3)") (class "Default")
      (node (ref "JP1") (pin "3") (pinfunction "3_3") (pintype "passive"))
    )
    (net (code "62") (name "unconnected-(JP1-Pad4)") (class "Default")
      (node (ref "JP1") (pin "4") (pinfunction "4_4") (pintype "passive"))
    )
    (net (code "63") (name "unconnected-(U1-Pad4_TIMEPULSE)") (class "Default")
      (node (ref "U1") (pin "4_TIMEPULSE") (pinfunction "4_TIMEPULSE_4_TIMEPULSE") (pintype "bidirectional"))
    )
    (net (code "64") (name "unconnected-(U1-Pad5_EXTINT0)") (class "Default")
      (node (ref "U1") (pin "5_EXTINT0") (pinfunction "5_EXTINT0_5_EXTINT0") (pintype "bidirectional"))
    )
    (net (code "65") (name "unconnected-(U1-Pad13_ANTON)") (class "Default")
      (node (ref "U1") (pin "13_ANTON") (pinfunction "13_ANTON_13_ANTON") (pintype "bidirectional"))
    )
    (net (code "66") (name "unconnected-(U1-Pad15_RESERVED)") (class "Default")
      (node (ref "U1") (pin "15_RESERVED") (pinfunction "15_RESERVED_15_RESERVED") (pintype "bidirectional"))
    )
    (net (code "67") (name "unconnected-(U1-Pad18_RESERVED)") (class "Default")
      (node (ref "U1") (pin "18_RESERVED") (pinfunction "18_RESERVED_18_RESERVED") (pintype "bidirectional"))
    )
    (net (code "68") (name "unconnected-(U2-PadRFOUT)") (class "Default")
      (node (ref "U2") (pin "RFOUT") (pinfunction "RFOUT_RFOUT") (pintype "bidirectional"))
    )
  )
)
